# Smokehouse_thermometer.net
KiCad netlist of a schematic drawn in Altium Designer
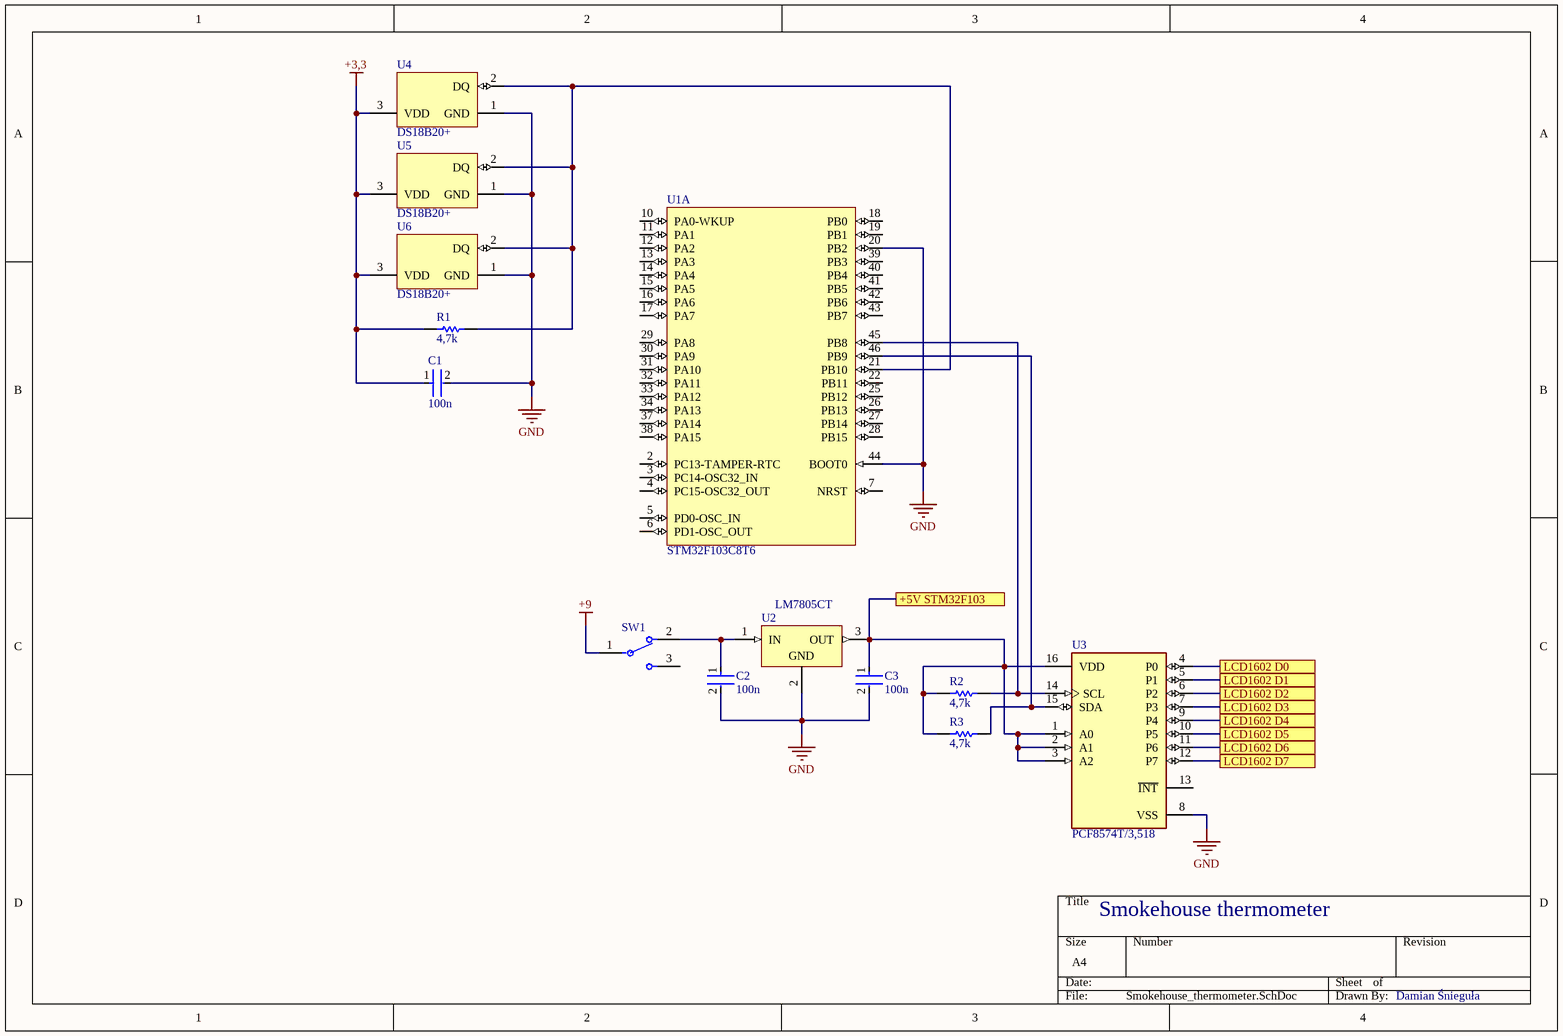
[diagram p0: Smokehouse_thermometer.SchDoc]

(export (version "E")
  (design (tool "Eeschema 10.0.6"))
  (components
    (comp (ref "C1")
      (value "100n")
      (footprint "FP-C0402-BB-MFG")
      (description "C0402 0.10 μF X5R 10.00% 10 V")
      (fields (field (name "MANUFACTURER") "Kemet"))
      (libsource (lib "Altium Content Vault") (part "b4654b650e69147ec39a6b967a45e02"))
    )
    (comp (ref "C2")
      (value "100n")
      (footprint "FP-C0402-BB-MFG")
      (description "C0402 0.10 μF X5R 10.00% 10 V")
      (fields (field (name "MANUFACTURER") "Kemet"))
      (libsource (lib "Altium Content Vault") (part "b4654b650e69147ec39a6b967a45e02"))
    )
    (comp (ref "C3")
      (value "100n")
      (footprint "FP-C0402-BB-MFG")
      (description "C0402 0.10 μF X5R 10.00% 10 V")
      (fields (field (name "MANUFACTURER") "Kemet"))
      (libsource (lib "Altium Content Vault") (part "b4654b650e69147ec39a6b967a45e02"))
    )
    (comp (ref "R1")
      (value "4,7k")
      (footprint "RESC1609X50X30NL8T20")
      (description "Chip Resistor, 0 Ohm, Jumper, 100 mW, -55 to 155 degC, 0603 (1608 Metric), RoHS, Tape and Reel")
      (fields (field (name "MANUFACTURER") "Vishay Semiconductor"))
      (libsource (lib "Altium Content Vault") (part "RES-2"))
    )
    (comp (ref "R2")
      (value "4,7k")
      (footprint "RESC1609X50X30NL8T20")
      (description "Chip Resistor, 0 Ohm, Jumper, 100 mW, -55 to 155 degC, 0603 (1608 Metric), RoHS, Tape and Reel")
      (fields (field (name "MANUFACTURER") "Vishay Semiconductor"))
      (libsource (lib "Altium Content Vault") (part "RES-2"))
    )
    (comp (ref "R3")
      (value "4,7k")
      (footprint "RESC1609X50X30NL8T20")
      (description "Chip Resistor, 0 Ohm, Jumper, 100 mW, -55 to 155 degC, 0603 (1608 Metric), RoHS, Tape and Reel")
      (fields (field (name "MANUFACTURER") "Vishay Semiconductor"))
      (libsource (lib "Altium Content Vault") (part "RES-2"))
    )
    (comp (ref "SW1")
      (value "A105SYCB04")
      (footprint "FP-A105SYCB04-MFG")
      (description "SWITCH TOGGLE SPDT 0.4VA 20V")
      (libsource (lib "Altium Content Vault") (part "edb4360d59316bed191fd4b931ffec7"))
    )
    (comp (ref "U1")
      (value "STM32F103C8T6")
      (footprint "STM-LQFP48_L")
      (libsource (lib "Altium Content Vault") (part "MC-ARM-STM32F103X8_B-SQ48"))
    )
    (comp (ref "U2")
      (value "LM7805CT")
      (footprint "FAIR-TO-220-3")
      (description "Positive Voltage Regulator, 5 V, 1 A, -40 to 125 degC, 3-Pin TO-220, RoHS, Tube")
      (fields (field (name "MANUFACTURER") "FairchildSemiconductor"))
      (libsource (lib "Altium Content Vault") (part "FAIR-LM7805CT-TO220-3"))
    )
    (comp (ref "U3")
      (value "PCF8574T/3,518")
      (footprint "FP-SOT162-1-MFG")
      (description "I/O Expander 8 I²C 100kHz 16-SO")
      (fields (field (name "MANUFACTURER") "NXP Semiconductors"))
      (libsource (lib "Altium Content Vault") (part "f7fde53ce59de981fb0b266a4e103eb"))
    )
    (comp (ref "U4")
      (value "DS18B20+")
      (footprint "Q3+1")
      (libsource (lib "Altium Content Vault") (part "SEN-TEMP-DS1821-SIL3"))
    )
    (comp (ref "U5")
      (value "DS18B20+")
      (footprint "Q3+1")
      (libsource (lib "Altium Content Vault") (part "SEN-TEMP-DS1821-SIL3"))
    )
    (comp (ref "U6")
      (value "DS18B20+")
      (footprint "Q3+1")
      (libsource (lib "Altium Content Vault") (part "SEN-TEMP-DS1821-SIL3"))
    )
  )
  (nets
    (net (code "1") (name "+3,3") (class "Default")
      (node (ref "C1") (pin "1") (pinfunction "1_1") (pintype "passive"))
      (node (ref "R1") (pin "1") (pinfunction "1_1") (pintype "passive"))
      (node (ref "U4") (pin "3") (pinfunction "VDD_3") (pintype "power_in"))
      (node (ref "U5") (pin "3") (pinfunction "VDD_3") (pintype "power_in"))
      (node (ref "U6") (pin "3") (pinfunction "VDD_3") (pintype "power_in"))
    )
    (net (code "2") (name "+9") (class "Default")
      (node (ref "SW1") (pin "1") (pinfunction "1_1") (pintype "passive"))
    )
    (net (code "3") (name "/+5V STM32F103") (class "Default")
      (node (ref "C3") (pin "1") (pinfunction "1_1") (pintype "passive"))
      (node (ref "R2") (pin "1") (pinfunction "1_1") (pintype "passive"))
      (node (ref "R3") (pin "1") (pinfunction "1_1") (pintype "passive"))
      (node (ref "U2") (pin "3") (pinfunction "OUT_3") (pintype "output"))
      (node (ref "U3") (pin "1") (pinfunction "A0_1") (pintype "input"))
      (node (ref "U3") (pin "16") (pinfunction "VDD_16") (pintype "power_in"))
      (node (ref "U3") (pin "2") (pinfunction "A1_2") (pintype "input"))
      (node (ref "U3") (pin "3") (pinfunction "A2_3") (pintype "input"))
    )
    (net (code "4") (name "/LCD1602 D0") (class "Default")
      (node (ref "U3") (pin "4") (pinfunction "P0_4") (pintype "bidirectional"))
    )
    (net (code "5") (name "/LCD1602 D1") (class "Default")
      (node (ref "U3") (pin "5") (pinfunction "P1_5") (pintype "bidirectional"))
    )
    (net (code "6") (name "/LCD1602 D2") (class "Default")
      (node (ref "U3") (pin "6") (pinfunction "P2_6") (pintype "bidirectional"))
    )
    (net (code "7") (name "/LCD1602 D3") (class "Default")
      (node (ref "U3") (pin "7") (pinfunction "P3_7") (pintype "bidirectional"))
    )
    (net (code "8") (name "/LCD1602 D4") (class "Default")
      (node (ref "U3") (pin "9") (pinfunction "P4_9") (pintype "bidirectional"))
    )
    (net (code "9") (name "/LCD1602 D5") (class "Default")
      (node (ref "U3") (pin "10") (pinfunction "P5_10") (pintype "bidirectional"))
    )
    (net (code "10") (name "/LCD1602 D6") (class "Default")
      (node (ref "U3") (pin "11") (pinfunction "P6_11") (pintype "bidirectional"))
    )
    (net (code "11") (name "/LCD1602 D7") (class "Default")
      (node (ref "U3") (pin "12") (pinfunction "P7_12") (pintype "bidirectional"))
    )
    (net (code "12") (name "GND") (class "Default")
      (node (ref "C1") (pin "2") (pinfunction "2_2") (pintype "passive"))
      (node (ref "C2") (pin "2") (pinfunction "2_2") (pintype "passive"))
      (node (ref "C3") (pin "2") (pinfunction "2_2") (pintype "passive"))
      (node (ref "U1") (pin "20") (pinfunction "PB2_20") (pintype "bidirectional"))
      (node (ref "U1") (pin "44") (pinfunction "BOOT0_44") (pintype "input"))
      (node (ref "U2") (pin "2") (pinfunction "GND_2") (pintype "power_in"))
      (node (ref "U3") (pin "8") (pinfunction "VSS_8") (pintype "power_in"))
      (node (ref "U4") (pin "1") (pinfunction "GND_1") (pintype "power_in"))
      (node (ref "U5") (pin "1") (pinfunction "GND_1") (pintype "power_in"))
      (node (ref "U6") (pin "1") (pinfunction "GND_1") (pintype "power_in"))
    )
    (net (code "13") (name "Net-(U1A-PB8)") (class "Default")
      (node (ref "R2") (pin "2") (pinfunction "2_2") (pintype "passive"))
      (node (ref "U1") (pin "45") (pinfunction "PB8_45") (pintype "bidirectional"))
      (node (ref "U3") (pin "14") (pinfunction "SCL_14") (pintype "input"))
    )
    (net (code "14") (name "Net-(U1A-PB9)") (class "Default")
      (node (ref "R3") (pin "2") (pinfunction "2_2") (pintype "passive"))
      (node (ref "U1") (pin "46") (pinfunction "PB9_46") (pintype "bidirectional"))
      (node (ref "U3") (pin "15") (pinfunction "SDA_15") (pintype "bidirectional"))
    )
    (net (code "15") (name "Net-(U1A-PB10)") (class "Default")
      (node (ref "R1") (pin "2") (pinfunction "2_2") (pintype "passive"))
      (node (ref "U1") (pin "21") (pinfunction "PB10_21") (pintype "bidirectional"))
      (node (ref "U4") (pin "2") (pinfunction "DQ_2") (pintype "bidirectional"))
      (node (ref "U5") (pin "2") (pinfunction "DQ_2") (pintype "bidirectional"))
      (node (ref "U6") (pin "2") (pinfunction "DQ_2") (pintype "bidirectional"))
    )
    (net (code "16") (name "Net-(U2-IN)") (class "Default")
      (node (ref "C2") (pin "1") (pinfunction "1_1") (pintype "passive"))
      (node (ref "SW1") (pin "2") (pinfunction "2_2") (pintype "passive"))
      (node (ref "U2") (pin "1") (pinfunction "IN_1") (pintype "input"))
    )
    (net (code "17") (name "unconnected-(SW1-Pad3)") (class "Default")
      (node (ref "SW1") (pin "3") (pinfunction "3_3") (pintype "passive"))
    )
    (net (code "18") (name "unconnected-(U1A-NRST-Pad7)") (class "Default")
      (node (ref "U1") (pin "7") (pinfunction "NRST_7") (pintype "bidirectional"))
    )
    (net (code "19") (name "unconnected-(U1A-PA0-WKUP-Pad10)") (class "Default")
      (node (ref "U1") (pin "10") (pinfunction "PA0-WKUP_10") (pintype "bidirectional"))
    )
    (net (code "20") (name "unconnected-(U1A-PA1-Pad11)") (class "Default")
      (node (ref "U1") (pin "11") (pinfunction "PA1_11") (pintype "bidirectional"))
    )
    (net (code "21") (name "unconnected-(U1A-PA2-Pad12)") (class "Default")
      (node (ref "U1") (pin "12") (pinfunction "PA2_12") (pintype "bidirectional"))
    )
    (net (code "22") (name "unconnected-(U1A-PA3-Pad13)") (class "Default")
      (node (ref "U1") (pin "13") (pinfunction "PA3_13") (pintype "bidirectional"))
    )
    (net (code "23") (name "unconnected-(U1A-PA4-Pad14)") (class "Default")
      (node (ref "U1") (pin "14") (pinfunction "PA4_14") (pintype "bidirectional"))
    )
    (net (code "24") (name "unconnected-(U1A-PA5-Pad15)") (class "Default")
      (node (ref "U1") (pin "15") (pinfunction "PA5_15") (pintype "bidirectional"))
    )
    (net (code "25") (name "unconnected-(U1A-PA6-Pad16)") (class "Default")
      (node (ref "U1") (pin "16") (pinfunction "PA6_16") (pintype "bidirectional"))
    )
    (net (code "26") (name "unconnected-(U1A-PA7-Pad17)") (class "Default")
      (node (ref "U1") (pin "17") (pinfunction "PA7_17") (pintype "bidirectional"))
    )
    (net (code "27") (name "unconnected-(U1A-PA8-Pad29)") (class "Default")
      (node (ref "U1") (pin "29") (pinfunction "PA8_29") (pintype "bidirectional"))
    )
    (net (code "28") (name "unconnected-(U1A-PA9-Pad30)") (class "Default")
      (node (ref "U1") (pin "30") (pinfunction "PA9_30") (pintype "bidirectional"))
    )
    (net (code "29") (name "unconnected-(U1A-PA10-Pad31)") (class "Default")
      (node (ref "U1") (pin "31") (pinfunction "PA10_31") (pintype "bidirectional"))
    )
    (net (code "30") (name "unconnected-(U1A-PA11-Pad32)") (class "Default")
      (node (ref "U1") (pin "32") (pinfunction "PA11_32") (pintype "bidirectional"))
    )
    (net (code "31") (name "unconnected-(U1A-PA12-Pad33)") (class "Default")
      (node (ref "U1") (pin "33") (pinfunction "PA12_33") (pintype "bidirectional"))
    )
    (net (code "32") (name "unconnected-(U1A-PA13-Pad34)") (class "Default")
      (node (ref "U1") (pin "34") (pinfunction "PA13_34") (pintype "bidirectional"))
    )
    (net (code "33") (name "unconnected-(U1A-PA14-Pad37)") (class "Default")
      (node (ref "U1") (pin "37") (pinfunction "PA14_37") (pintype "bidirectional"))
    )
    (net (code "34") (name "unconnected-(U1A-PA15-Pad38)") (class "Default")
      (node (ref "U1") (pin "38") (pinfunction "PA15_38") (pintype "bidirectional"))
    )
    (net (code "35") (name "unconnected-(U1A-PB0-Pad18)") (class "Default")
      (node (ref "U1") (pin "18") (pinfunction "PB0_18") (pintype "bidirectional"))
    )
    (net (code "36") (name "unconnected-(U1A-PB1-Pad19)") (class "Default")
      (node (ref "U1") (pin "19") (pinfunction "PB1_19") (pintype "bidirectional"))
    )
    (net (code "37") (name "unconnected-(U1A-PB3-Pad39)") (class "Default")
      (node (ref "U1") (pin "39") (pinfunction "PB3_39") (pintype "bidirectional"))
    )
    (net (code "38") (name "unconnected-(U1A-PB4-Pad40)") (class "Default")
      (node (ref "U1") (pin "40") (pinfunction "PB4_40") (pintype "bidirectional"))
    )
    (net (code "39") (name "unconnected-(U1A-PB5-Pad41)") (class "Default")
      (node (ref "U1") (pin "41") (pinfunction "PB5_41") (pintype "bidirectional"))
    )
    (net (code "40") (name "unconnected-(U1A-PB6-Pad42)") (class "Default")
      (node (ref "U1") (pin "42") (pinfunction "PB6_42") (pintype "bidirectional"))
    )
    (net (code "41") (name "unconnected-(U1A-PB7-Pad43)") (class "Default")
      (node (ref "U1") (pin "43") (pinfunction "PB7_43") (pintype "bidirectional"))
    )
    (net (code "42") (name "unconnected-(U1A-PB11-Pad22)") (class "Default")
      (node (ref "U1") (pin "22") (pinfunction "PB11_22") (pintype "bidirectional"))
    )
    (net (code "43") (name "unconnected-(U1A-PB12-Pad25)") (class "Default")
      (node (ref "U1") (pin "25") (pinfunction "PB12_25") (pintype "bidirectional"))
    )
    (net (code "44") (name "unconnected-(U1A-PB13-Pad26)") (class "Default")
      (node (ref "U1") (pin "26") (pinfunction "PB13_26") (pintype "bidirectional"))
    )
    (net (code "45") (name "unconnected-(U1A-PB14-Pad27)") (class "Default")
      (node (ref "U1") (pin "27") (pinfunction "PB14_27") (pintype "bidirectional"))
    )
    (net (code "46") (name "unconnected-(U1A-PB15-Pad28)") (class "Default")
      (node (ref "U1") (pin "28") (pinfunction "PB15_28") (pintype "bidirectional"))
    )
    (net (code "47") (name "unconnected-(U1A-PC13-TAMPER-RTC-Pad2)") (class "Default")
      (node (ref "U1") (pin "2") (pinfunction "PC13-TAMPER-RTC_2") (pintype "bidirectional"))
    )
    (net (code "48") (name "unconnected-(U1A-PC14-OSC32_IN-Pad3)") (class "Default")
      (node (ref "U1") (pin "3") (pinfunction "PC14-OSC32_IN_3") (pintype "bidirectional"))
    )
    (net (code "49") (name "unconnected-(U1A-PC15-OSC32_OUT-Pad4)") (class "Default")
      (node (ref "U1") (pin "4") (pinfunction "PC15-OSC32_OUT_4") (pintype "bidirectional"))
    )
    (net (code "50") (name "unconnected-(U1A-PD0-OSC_IN-Pad5)") (class "Default")
      (node (ref "U1") (pin "5") (pinfunction "PD0-OSC_IN_5") (pintype "bidirectional"))
    )
    (net (code "51") (name "unconnected-(U1A-PD1-OSC_OUT-Pad6)") (class "Default")
      (node (ref "U1") (pin "6") (pinfunction "PD1-OSC_OUT_6") (pintype "bidirectional"))
    )
    (net (code "52") (name "unconnected-(U3-~{INT}-Pad13)") (class "Default")
      (node (ref "U3") (pin "13") (pinfunction "~{INT}_13") (pintype "open_collector"))
    )
  )
)
